# Thruster_Power.net
KiCad netlist of a schematic drawn in Altium Designer
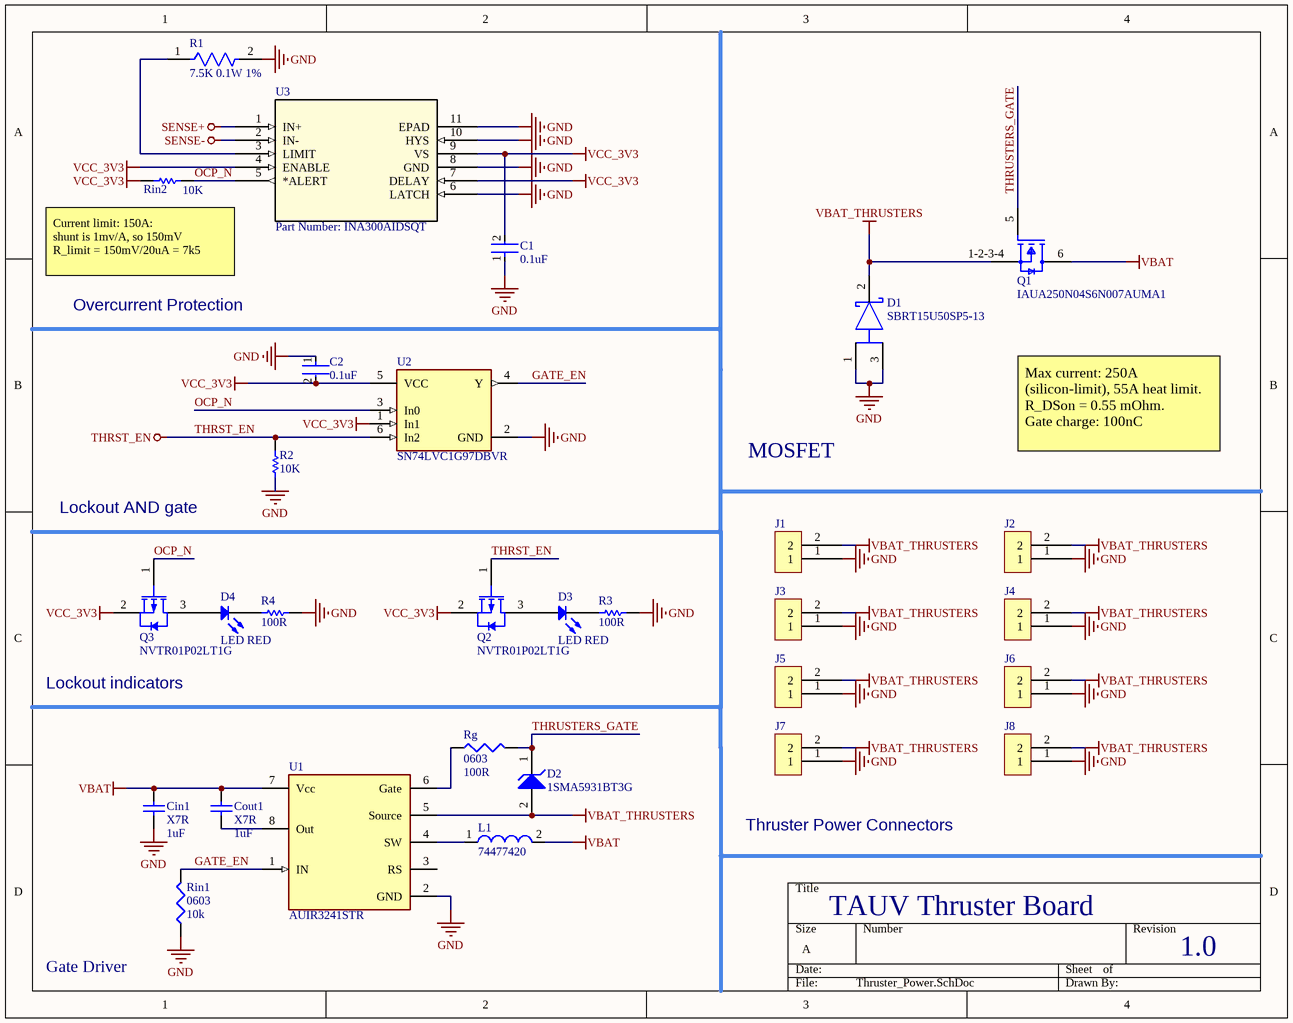
[diagram p0: Thruster_Power.SchDoc]

(export (version "E")
  (design (tool "Eeschema 10.0.6"))
  (components
    (comp (ref "C1")
      (value "0.1uF")
      (footprint "FP-C0603C-CF-MFG")
      (description "CAP CER 0.1UF 10V X7R 0603")
      (fields (field (name "TOLERANCE") "0.1") (field (name "MANUFACTURER PART NUMBER") "C0603C104K8RACTU"))
      (libsource (lib "Altium Content Vault") (part "b4654b650e69147ec39a6b967a45e02"))
    )
    (comp (ref "C2")
      (value "0.1uF")
      (footprint "FP-C0603C-CF-MFG")
      (description "CAP CER 0.1UF 10V X7R 0603")
      (fields (field (name "TOLERANCE") "0.1") (field (name "MANUFACTURER PART NUMBER") "C0603C104K8RACTU"))
      (libsource (lib "Altium Content Vault") (part "b4654b650e69147ec39a6b967a45e02"))
    )
    (comp (ref "Cin1")
      (value "X7R")
      (footprint "C0805")
      (description "Capacitor")
      (fields (field (name "ALTIUM_VALUE") "1uF") (field (name "PUBLISHER") "Altium Limited"))
      (libsource (lib "Miscellaneous Devices") (part "Cap"))
    )
    (comp (ref "Cout1")
      (value "X7R")
      (footprint "C0805")
      (description "Capacitor")
      (fields (field (name "ALTIUM_VALUE") "1uF") (field (name "PUBLISHER") "Altium Limited"))
      (libsource (lib "Miscellaneous Devices") (part "Cap"))
    )
    (comp (ref "D1")
      (value "SBRT15U50SP5-13")
      (footprint "FP-PowerDI5-MFG")
      (description "50V 15A Rectifier Schottky Diode")
      (fields
        (field (name "OCTOPART") "https://octopart.com/pds3200-13-diodes+inc.-332544")
        (field (name "MANUFACTURER") "Diodes Inc.")
      )
      (libsource (lib "Altium Content Vault") (part "0222f6c3f9f8f3c07decc49f824026a"))
    )
    (comp (ref "D2")
      (value "1SMA5931BT3G")
      (footprint "ONSC-SMA-2-403D-02_F_V")
      (description "1.5 W Zener Voltage Regulator, 2-Pin SMA, Pb-Free, Tape and Reel")
      (fields (field (name "MANUFACTURER") "On Semiconductor"))
      (libsource (lib "Altium Content Vault") (part "ONSC-K1A2-2"))
    )
    (comp (ref "D3")
      (value "LED RED")
      (footprint "C0805")
      (description "led\r\n LTST-C171KRKT")
      (fields
        (field (name "MANUFACTURER") "Lite-On Inc.")
        (field (name "MANUFACTURER PART NUMBER") "LTST-C171KRKT")
      )
      (libsource (lib "CMR_Miscellaneous_Devices") (part "LED0"))
    )
    (comp (ref "D4")
      (value "LED RED")
      (footprint "C0805")
      (description "led\r\n LTST-C171KRKT")
      (fields
        (field (name "MANUFACTURER") "Lite-On Inc.")
        (field (name "MANUFACTURER PART NUMBER") "LTST-C171KRKT")
      )
      (libsource (lib "CMR_Miscellaneous_Devices") (part "LED0"))
    )
    (comp (ref "J1")
      (value "~")
      (footprint "2-pin Megafit RA")
      (libsource (lib "TAUV-Lib") (part "2-pin megafit"))
    )
    (comp (ref "J2")
      (value "~")
      (footprint "2-pin Megafit RA")
      (libsource (lib "TAUV-Lib") (part "2-pin megafit"))
    )
    (comp (ref "J3")
      (value "~")
      (footprint "2-pin Megafit RA")
      (libsource (lib "TAUV-Lib") (part "2-pin megafit"))
    )
    (comp (ref "J4")
      (value "~")
      (footprint "2-pin Megafit RA")
      (libsource (lib "TAUV-Lib") (part "2-pin megafit"))
    )
    (comp (ref "J5")
      (value "~")
      (footprint "2-pin Megafit RA")
      (libsource (lib "TAUV-Lib") (part "2-pin megafit"))
    )
    (comp (ref "J6")
      (value "~")
      (footprint "2-pin Megafit RA")
      (libsource (lib "TAUV-Lib") (part "2-pin megafit"))
    )
    (comp (ref "J7")
      (value "~")
      (footprint "2-pin Megafit RA")
      (libsource (lib "TAUV-Lib") (part "2-pin megafit"))
    )
    (comp (ref "J8")
      (value "~")
      (footprint "2-pin Megafit RA")
      (libsource (lib "TAUV-Lib") (part "2-pin megafit"))
    )
    (comp (ref "L1")
      (value "74477420")
      (footprint "WE-PD2-M")
      (description "SMD Power Inductor WE-PD2, L = 100 µH")
      (libsource (lib "Altium Content Vault") (part "PAS-IND-INDUCTOR-2"))
    )
    (comp (ref "Q1")
      (value "IAUA250N04S6N007AUMA1")
      (footprint "FP-PG-HSOF-5-MFG")
      (description "MOSFET_(20V 40V) PG-HSOF-5")
      (libsource (lib "Altium Content Vault") (part "1da00a00be1a6cc7dc21b23752af3b0"))
    )
    (comp (ref "Q2")
      (value "NVTR01P02LT1G")
      (footprint "ONSC-SOT-23-3-318-08_V")
      (description "Power MOSFET, -20 V, -1.3 A, P-Channel, 3-Pin SOT-23, Pb-Free, Tape and Reel")
      (fields (field (name "MANUFACTURER") "On Semiconductor"))
      (libsource (lib "Altium Content Vault") (part "ONSC-PMOS-G1S2D3-3_D"))
    )
    (comp (ref "Q3")
      (value "NVTR01P02LT1G")
      (footprint "ONSC-SOT-23-3-318-08_V")
      (description "Power MOSFET, -20 V, -1.3 A, P-Channel, 3-Pin SOT-23, Pb-Free, Tape and Reel")
      (fields (field (name "MANUFACTURER") "On Semiconductor"))
      (libsource (lib "Altium Content Vault") (part "ONSC-PMOS-G1S2D3-3_D"))
    )
    (comp (ref "R1")
      (value "7.5K 0.1W 1%")
      (footprint "FP-ERJ3EK-MFG")
      (description "RES SMD 7.5K OHM 1% 1/10W 0603")
      (fields (field (name "TOLERANCE") "1%"))
      (libsource (lib "Altium Content Vault") (part "1029c3af85768c4190bb7ad29bc67b5"))
    )
    (comp (ref "R2")
      (value "10K")
      (footprint "RESC0603(1608)_N")
      (description "10K 0.1W 5% 0603 (1608 Metric)  SMD")
      (fields (field (name "TOLERANCE") "5 %") (field (name "POWER") "0.1 W"))
      (libsource (lib "Altium Content Vault") (part "RES"))
    )
    (comp (ref "R3")
      (value "100R")
      (footprint "RESC1609X50X30NL10T20")
      (description "100R 0.1W 5%")
      (fields (field (name "PART NUMBER") "CRCW0603100RJNTA") (field (name "MANUFACTURER") "Vishay Dale"))
      (libsource (lib "Altium Content Vault") (part "RES"))
    )
    (comp (ref "R4")
      (value "100R")
      (footprint "RESC1609X50X30NL10T20")
      (description "100R 0.1W 5%")
      (fields (field (name "PART NUMBER") "CRCW0603100RJNTA") (field (name "MANUFACTURER") "Vishay Dale"))
      (libsource (lib "Altium Content Vault") (part "RES"))
    )
    (comp (ref "Rg")
      (value "0603")
      (footprint "J1-0603")
      (description "Resistor")
      (fields (field (name "ALTIUM_VALUE") "100R") (field (name "PUBLISHER") "Altium Limited"))
      (libsource (lib "Miscellaneous Devices") (part "Res3"))
    )
    (comp (ref "Rin1")
      (value "0603")
      (footprint "J1-0603")
      (description "Resistor")
      (fields (field (name "ALTIUM_VALUE") "10k") (field (name "PUBLISHER") "Altium Limited"))
      (libsource (lib "Miscellaneous Devices") (part "Res3"))
    )
    (comp (ref "Rin2")
      (value "10K")
      (footprint "RESC0603(1608)_N")
      (description "10K 0.1W 5% 0603 (1608 Metric)  SMD")
      (fields (field (name "TOLERANCE") "5 %") (field (name "POWER") "0.1 W"))
      (libsource (lib "Altium Content Vault") (part "RES"))
    )
    (comp (ref "U1")
      (value "AUIR3241STR")
      (footprint "FP-PG-DSO-8-MFG")
      (description "IC GATE DRVR HIGH-SIDE 8SO")
      (libsource (lib "Altium Content Vault") (part "34ae5cb6024c322bdcbf0313f74d293"))
    )
    (comp (ref "U2")
      (value "SN74LVC1G97DBVR")
      (footprint "FP-DBV0006A-MFG")
      (description "IC CONFIG MULT-FUNC GATE SOT23-6")
      (fields
        (field (name "OCTOPART") "https://octopart.com/sn74lvc1g97dbvr-texas+instruments-464842")
        (field (name "MANUFACTURER") "Texas Instruments")
      )
      (libsource (lib "Altium Content Vault") (part "a1876f62f2ab2790f28bb26e63f2887"))
    )
    (comp (ref "U3")
      (value "Part Number: INA300AIDSQT")
      (footprint "DSQ10_P9X1P5")
      (description "No Description Available")
      (fields
        (field (name "MANUFACTURER_PART_NUMBER") "INA300AIDSQT")
        (field (name "COPYRIGHT") "Copyright (C) 2018 Accelerated Designs. All rights reserved")
      )
      (libsource (lib "Tauv-Lib") (part "INA300AIDSQT"))
    )
  )
  (nets
    (net (code "1") (name "/GATE_EN") (class "Default")
      (node (ref "Rin1") (pin "2") (pinfunction "2_2") (pintype "passive"))
      (node (ref "U1") (pin "1") (pinfunction "IN_1") (pintype "input"))
      (node (ref "U2") (pin "4") (pinfunction "Y_4") (pintype "output"))
    )
    (net (code "2") (name "/OCP_N") (class "Default")
      (node (ref "Q3") (pin "1") (pinfunction "G_1") (pintype "passive"))
      (node (ref "Rin2") (pin "1") (pinfunction "1_1") (pintype "passive"))
      (node (ref "U2") (pin "3") (pinfunction "In0_3") (pintype "input"))
      (node (ref "U3") (pin "5") (pinfunction "*ALERT_5") (pintype "output"))
    )
    (net (code "3") (name "/THRUSTERS_GATE") (class "Default")
      (node (ref "D2") (pin "1") (pinfunction "K_1") (pintype "passive"))
      (node (ref "Q1") (pin "5") (pinfunction "G_5") (pintype "passive"))
      (node (ref "Rg") (pin "2") (pinfunction "2_2") (pintype "passive"))
    )
    (net (code "4") (name "GND") (class "Default")
      (node (ref "C1") (pin "1") (pinfunction "1_1") (pintype "passive"))
      (node (ref "C2") (pin "1") (pinfunction "1_1") (pintype "passive"))
      (node (ref "Cin1") (pin "1") (pinfunction "1_1") (pintype "passive"))
      (node (ref "D1") (pin "1") (pinfunction "A_1") (pintype "passive"))
      (node (ref "D1") (pin "3") (pinfunction "A_3") (pintype "passive"))
      (node (ref "J1") (pin "1") (pinfunction "1_1") (pintype "passive"))
      (node (ref "J2") (pin "1") (pinfunction "1_1") (pintype "passive"))
      (node (ref "J3") (pin "1") (pinfunction "1_1") (pintype "passive"))
      (node (ref "J4") (pin "1") (pinfunction "1_1") (pintype "passive"))
      (node (ref "J5") (pin "1") (pinfunction "1_1") (pintype "passive"))
      (node (ref "J6") (pin "1") (pinfunction "1_1") (pintype "passive"))
      (node (ref "J7") (pin "1") (pinfunction "1_1") (pintype "passive"))
      (node (ref "J8") (pin "1") (pinfunction "1_1") (pintype "passive"))
      (node (ref "R1") (pin "2") (pinfunction "2_2") (pintype "passive"))
      (node (ref "R2") (pin "2") (pinfunction "2_2") (pintype "passive"))
      (node (ref "R3") (pin "2") (pinfunction "2_2") (pintype "passive"))
      (node (ref "R4") (pin "2") (pinfunction "2_2") (pintype "passive"))
      (node (ref "Rin1") (pin "1") (pinfunction "1_1") (pintype "passive"))
      (node (ref "U1") (pin "2") (pinfunction "GND_2") (pintype "power_in"))
      (node (ref "U2") (pin "2") (pinfunction "GND_2") (pintype "power_in"))
      (node (ref "U3") (pin "10") (pinfunction "HYS_10") (pintype "input"))
      (node (ref "U3") (pin "11") (pinfunction "EPAD_11") (pintype "passive"))
      (node (ref "U3") (pin "6") (pinfunction "LATCH_6") (pintype "input"))
      (node (ref "U3") (pin "8") (pinfunction "GND_8") (pintype "power_in"))
    )
    (net (code "5") (name "Net-(D3-A)") (class "Default")
      (node (ref "D3") (pin "2") (pinfunction "A_2") (pintype "passive"))
      (node (ref "Q2") (pin "3") (pinfunction "D_3") (pintype "passive"))
    )
    (net (code "6") (name "Net-(D3-K)") (class "Default")
      (node (ref "D3") (pin "1") (pinfunction "K_1") (pintype "passive"))
      (node (ref "R3") (pin "1") (pinfunction "1_1") (pintype "passive"))
    )
    (net (code "7") (name "Net-(D4-A)") (class "Default")
      (node (ref "D4") (pin "2") (pinfunction "A_2") (pintype "passive"))
      (node (ref "Q3") (pin "3") (pinfunction "D_3") (pintype "passive"))
    )
    (net (code "8") (name "Net-(D4-K)") (class "Default")
      (node (ref "D4") (pin "1") (pinfunction "K_1") (pintype "passive"))
      (node (ref "R4") (pin "1") (pinfunction "1_1") (pintype "passive"))
    )
    (net (code "9") (name "Net-(U1-Gate)") (class "Default")
      (node (ref "Rg") (pin "1") (pinfunction "1_1") (pintype "passive"))
      (node (ref "U1") (pin "6") (pinfunction "Gate_6") (pintype "passive"))
    )
    (net (code "10") (name "Net-(U1-Out)") (class "Default")
      (node (ref "Cout1") (pin "1") (pinfunction "1_1") (pintype "passive"))
      (node (ref "U1") (pin "8") (pinfunction "Out_8") (pintype "passive"))
    )
    (net (code "11") (name "Net-(U1-SW)") (class "Default")
      (node (ref "L1") (pin "1") (pinfunction "1_1") (pintype "passive"))
      (node (ref "U1") (pin "4") (pinfunction "SW_4") (pintype "passive"))
    )
    (net (code "12") (name "Net-(U3-LIMIT)") (class "Default")
      (node (ref "R1") (pin "1") (pinfunction "1_1") (pintype "passive"))
      (node (ref "U3") (pin "3") (pinfunction "LIMIT_3") (pintype "input"))
    )
    (net (code "13") (name "SENSE+") (class "Default")
      (node (ref "U3") (pin "1") (pinfunction "IN+_1") (pintype "input"))
    )
    (net (code "14") (name "SENSE-") (class "Default")
      (node (ref "U3") (pin "2") (pinfunction "IN-_2") (pintype "input"))
    )
    (net (code "15") (name "THRST_EN") (class "Default")
      (node (ref "Q2") (pin "1") (pinfunction "G_1") (pintype "passive"))
      (node (ref "R2") (pin "1") (pinfunction "1_1") (pintype "passive"))
      (node (ref "U2") (pin "6") (pinfunction "In2_6") (pintype "input"))
    )
    (net (code "16") (name "VBAT") (class "Default")
      (node (ref "Cin1") (pin "2") (pinfunction "2_2") (pintype "passive"))
      (node (ref "Cout1") (pin "2") (pinfunction "2_2") (pintype "passive"))
      (node (ref "L1") (pin "2") (pinfunction "2_2") (pintype "passive"))
      (node (ref "Q1") (pin "6") (pinfunction "D_6") (pintype "passive"))
      (node (ref "U1") (pin "7") (pinfunction "Vcc_7") (pintype "power_in"))
    )
    (net (code "17") (name "VBAT_THRUSTERS") (class "Default")
      (node (ref "D1") (pin "2") (pinfunction "C_2") (pintype "passive"))
      (node (ref "D2") (pin "2") (pinfunction "A_2") (pintype "passive"))
      (node (ref "J1") (pin "2") (pinfunction "2_2") (pintype "passive"))
      (node (ref "J2") (pin "2") (pinfunction "2_2") (pintype "passive"))
      (node (ref "J3") (pin "2") (pinfunction "2_2") (pintype "passive"))
      (node (ref "J4") (pin "2") (pinfunction "2_2") (pintype "passive"))
      (node (ref "J5") (pin "2") (pinfunction "2_2") (pintype "passive"))
      (node (ref "J6") (pin "2") (pinfunction "2_2") (pintype "passive"))
      (node (ref "J7") (pin "2") (pinfunction "2_2") (pintype "passive"))
      (node (ref "J8") (pin "2") (pinfunction "2_2") (pintype "passive"))
      (node (ref "Q1") (pin "1-2-3-4") (pinfunction "S_1-2-3-4") (pintype "passive"))
      (node (ref "U1") (pin "5") (pinfunction "Source_5") (pintype "passive"))
    )
    (net (code "18") (name "VCC_3V3") (class "Default")
      (node (ref "C1") (pin "2") (pinfunction "2_2") (pintype "passive"))
      (node (ref "C2") (pin "2") (pinfunction "2_2") (pintype "passive"))
      (node (ref "Q2") (pin "2") (pinfunction "S_2") (pintype "passive"))
      (node (ref "Q3") (pin "2") (pinfunction "S_2") (pintype "passive"))
      (node (ref "Rin2") (pin "2") (pinfunction "2_2") (pintype "passive"))
      (node (ref "U2") (pin "1") (pinfunction "In1_1") (pintype "input"))
      (node (ref "U2") (pin "5") (pinfunction "VCC_5") (pintype "power_in"))
      (node (ref "U3") (pin "4") (pinfunction "ENABLE_4") (pintype "input"))
      (node (ref "U3") (pin "7") (pinfunction "DELAY_7") (pintype "input"))
      (node (ref "U3") (pin "9") (pinfunction "VS_9") (pintype "power_in"))
    )
    (net (code "19") (name "unconnected-(U1-RS-Pad3)") (class "Default")
      (node (ref "U1") (pin "3") (pinfunction "RS_3") (pintype "passive"))
    )
  )
)
